# ProPrj_Electric_Dog.net
KiCad netlist of a schematic drawn in EasyEDA Pro
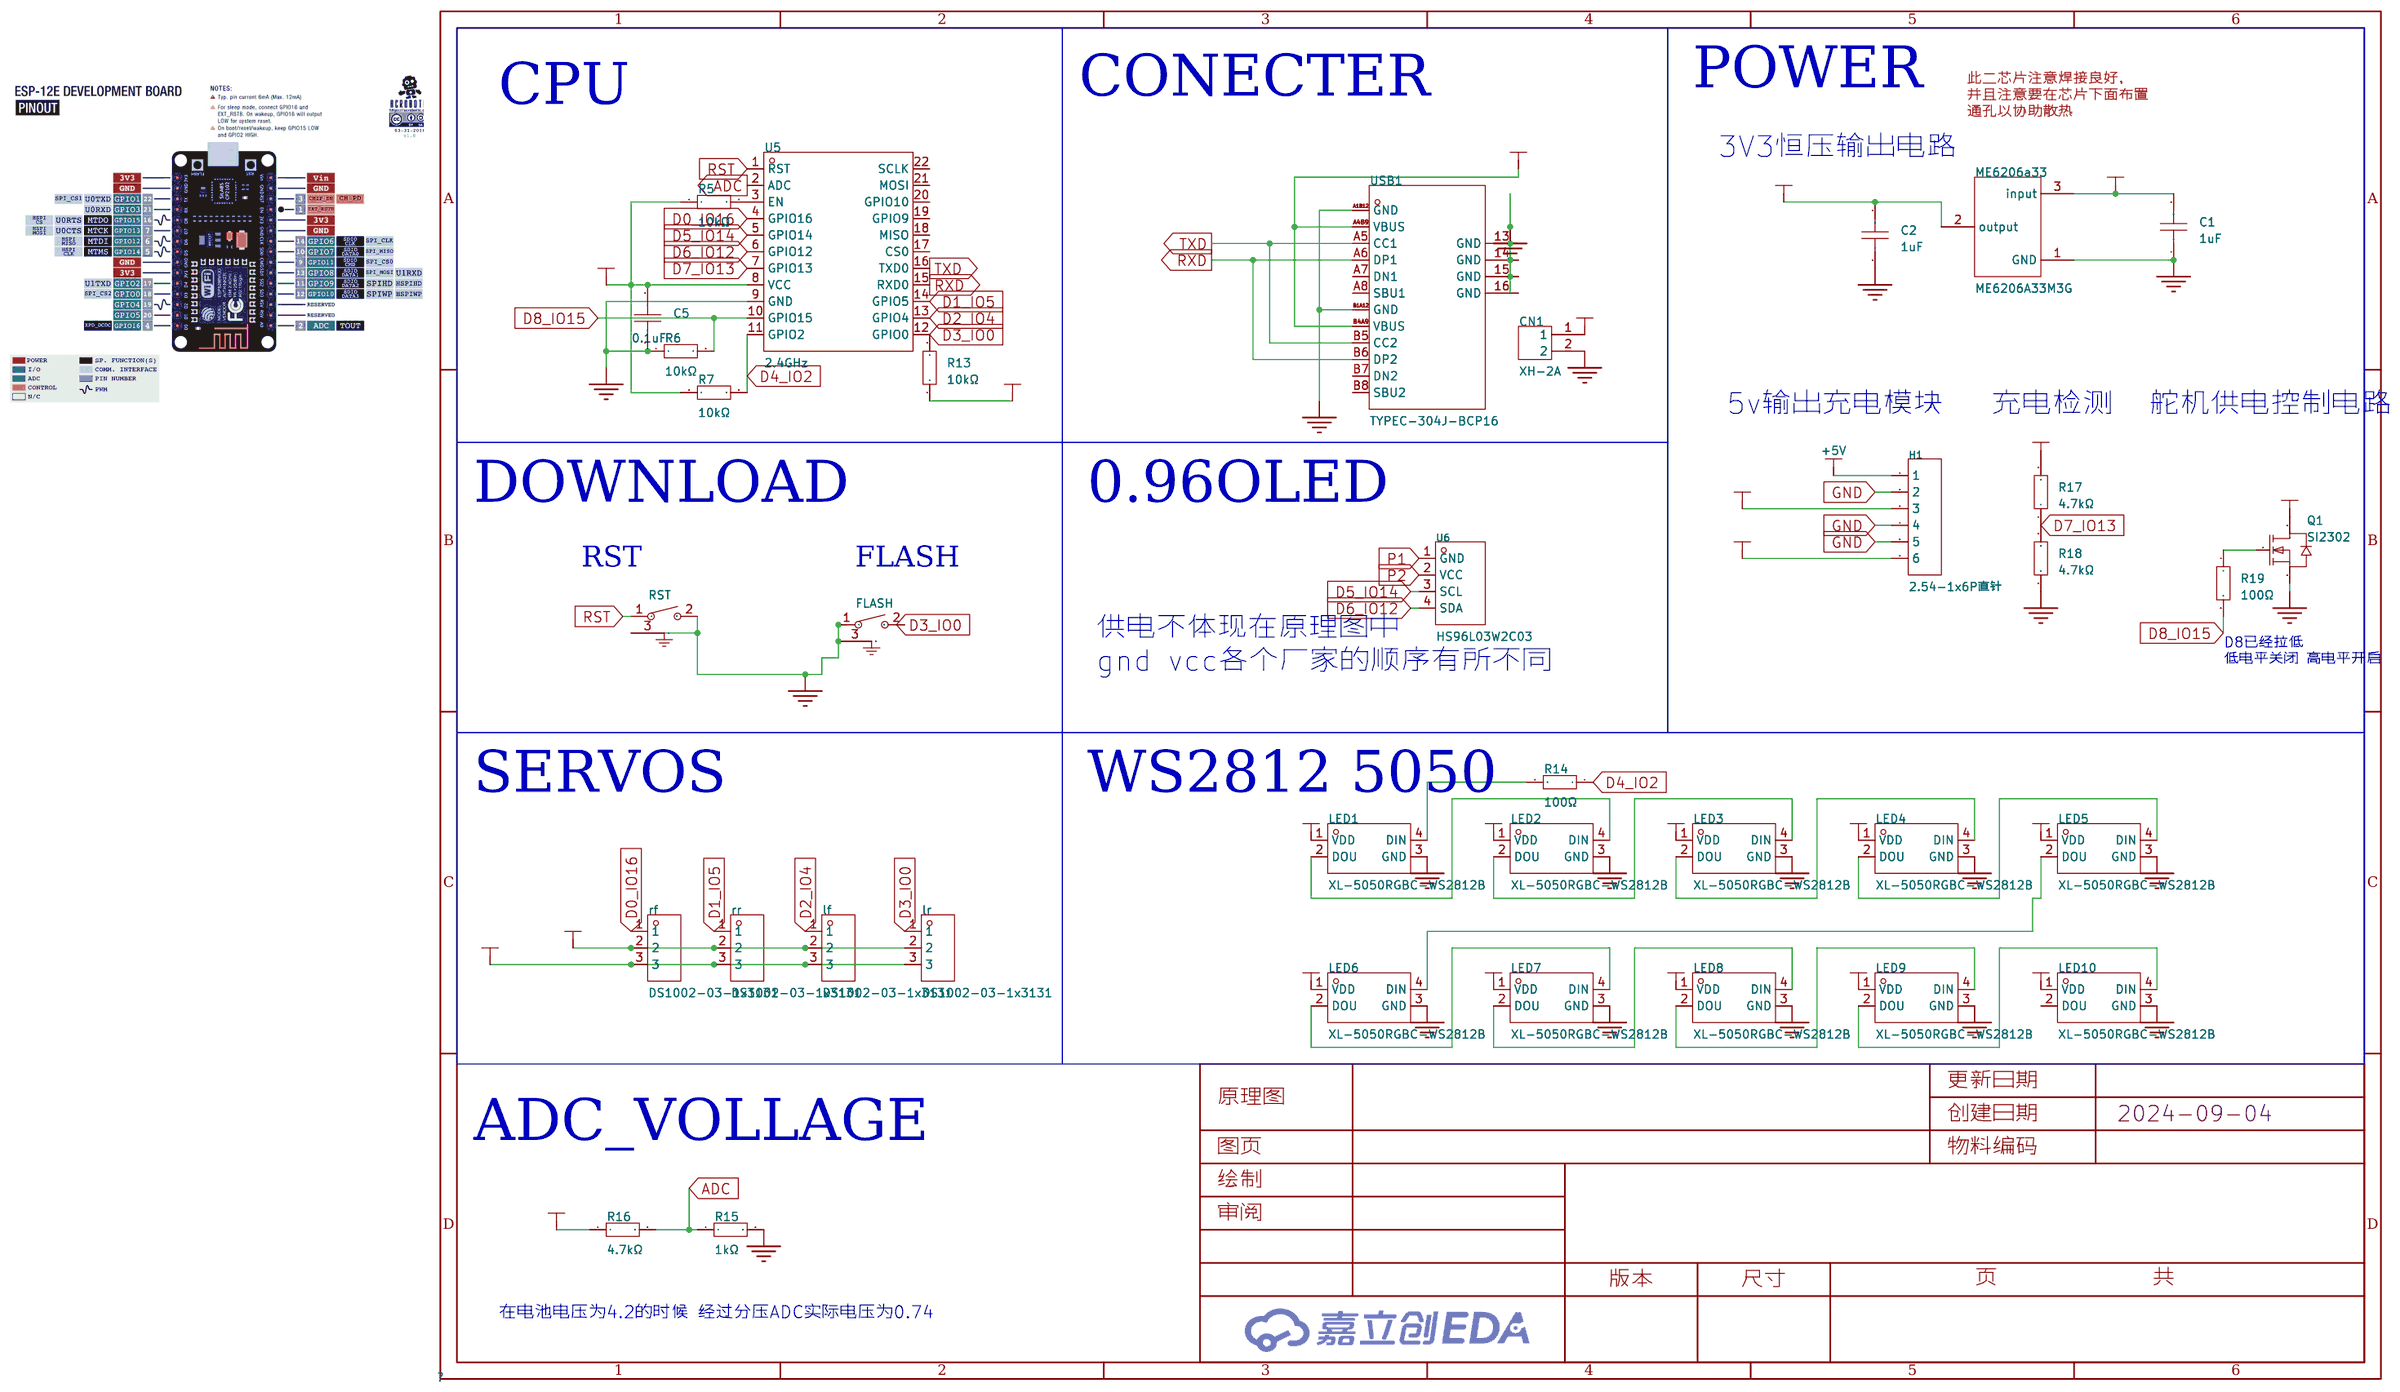
[diagram p0: schematic sheet]

(export (version "E")
  (design (tool "Eeschema 10.0.6"))
  (components
    (comp (ref "C1")
      (value "1uF")
      (footprint "easyedapro:C0603")
      (description "容值:1uF;精度:±10%;额定电压:50V;材质(温度系数):X5R;")
      (fields
        (field (name "Manufacturer Part") "CL10A105KB8NNNC")
        (field (name "Manufacturer") "SAMSUNG(三星)")
      )
      (libsource (lib "easyedapro") (part "CL10A105KB8NNNC"))
    )
    (comp (ref "C2")
      (value "1uF")
      (footprint "easyedapro:C0603")
      (description "容值:1uF;精度:±10%;额定电压:50V;材质(温度系数):X5R;")
      (fields
        (field (name "Manufacturer Part") "CL10A105KB8NNNC")
        (field (name "Manufacturer") "SAMSUNG(三星)")
      )
      (libsource (lib "easyedapro") (part "CL10A105KB8NNNC"))
    )
    (comp (ref "C5")
      (value "0.1uF")
      (footprint "easyedapro:C0603")
      (description "容值:0.1uF;精度:±10%;额定电压:50V;温度系数:-;")
      (fields
        (field (name "Manufacturer Part") "0603BB104K500NGT")
        (field (name "Manufacturer") "Knowles(楼氏)")
      )
      (libsource (lib "easyedapro") (part "0603BB104K500NGT"))
    )
    (comp (ref "CN1")
      (value "XH-2A")
      (footprint "easyedapro:CONN-TH_XH-2A")
      (description "插针结构:1x2P;间距:2.5mm;安装方式:-;参考系列:XH;总PIN数:2P;排数:1;每排PIN数:2;行距:-;触头材质:-;")
      (fields (field (name "Manufacturer") "BOOMELE(博穆精密)"))
      (libsource (lib "easyedapro") (part "XH-2A"))
    )
    (comp (ref "FLASH")
      (value "TS-1091B-A8B3-D2")
      (footprint "easyedapro:KEY-TH_L4.5-W6.5-P3.10_TS-1091B-A8B3-D2")
      (description "电路结构:单刀单掷;安装方式:卧插;作用力:250gf@±30gf;机械寿命:-;带支架:否;")
      (fields (field (name "Manufacturer") "Yuandi(元迪)"))
      (libsource (lib "easyedapro") (part "TS-1091B-A8B3-D2"))
    )
    (comp (ref "H1")
      (value "2.54-1x6P直针")
      (footprint "easyedapro:HDR-TH_6P-P2.54-V-M-1")
      (fields (field (name "Manufacturer") "BOOMELE(博穆精密)"))
      (libsource (lib "easyedapro") (part "Header-Male-2.54_1x6"))
    )
    (comp (ref "LED1")
      (value "XL-5050RGBC-WS2812B")
      (footprint "easyedapro:LED-SMD_4P-L5.0-W5.0-BL_XL-5050RGBC")
      (description "5050七彩幻彩透明贴片LED灯珠 5050 幻彩透明四脚 ws2812B 内置驱动IC")
      (fields (field (name "Manufacturer") "XINGLIGHT(成兴光)"))
      (libsource (lib "easyedapro") (part "XL-5050RGBC-WS2812B"))
    )
    (comp (ref "LED2")
      (value "XL-5050RGBC-WS2812B")
      (footprint "easyedapro:LED-SMD_4P-L5.0-W5.0-BL_XL-5050RGBC")
      (description "5050七彩幻彩透明贴片LED灯珠 5050 幻彩透明四脚 ws2812B 内置驱动IC")
      (fields (field (name "Manufacturer") "XINGLIGHT(成兴光)"))
      (libsource (lib "easyedapro") (part "XL-5050RGBC-WS2812B"))
    )
    (comp (ref "LED3")
      (value "XL-5050RGBC-WS2812B")
      (footprint "easyedapro:LED-SMD_4P-L5.0-W5.0-BL_XL-5050RGBC")
      (description "5050七彩幻彩透明贴片LED灯珠 5050 幻彩透明四脚 ws2812B 内置驱动IC")
      (fields (field (name "Manufacturer") "XINGLIGHT(成兴光)"))
      (libsource (lib "easyedapro") (part "XL-5050RGBC-WS2812B"))
    )
    (comp (ref "LED4")
      (value "XL-5050RGBC-WS2812B")
      (footprint "easyedapro:LED-SMD_4P-L5.0-W5.0-BL_XL-5050RGBC")
      (description "5050七彩幻彩透明贴片LED灯珠 5050 幻彩透明四脚 ws2812B 内置驱动IC")
      (fields (field (name "Manufacturer") "XINGLIGHT(成兴光)"))
      (libsource (lib "easyedapro") (part "XL-5050RGBC-WS2812B"))
    )
    (comp (ref "LED5")
      (value "XL-5050RGBC-WS2812B")
      (footprint "easyedapro:LED-SMD_4P-L5.0-W5.0-BL_XL-5050RGBC")
      (description "5050七彩幻彩透明贴片LED灯珠 5050 幻彩透明四脚 ws2812B 内置驱动IC")
      (fields (field (name "Manufacturer") "XINGLIGHT(成兴光)"))
      (libsource (lib "easyedapro") (part "XL-5050RGBC-WS2812B"))
    )
    (comp (ref "LED6")
      (value "XL-5050RGBC-WS2812B")
      (footprint "easyedapro:LED-SMD_4P-L5.0-W5.0-BL_XL-5050RGBC")
      (description "5050七彩幻彩透明贴片LED灯珠 5050 幻彩透明四脚 ws2812B 内置驱动IC")
      (fields (field (name "Manufacturer") "XINGLIGHT(成兴光)"))
      (libsource (lib "easyedapro") (part "XL-5050RGBC-WS2812B"))
    )
    (comp (ref "LED7")
      (value "XL-5050RGBC-WS2812B")
      (footprint "easyedapro:LED-SMD_4P-L5.0-W5.0-BL_XL-5050RGBC")
      (description "5050七彩幻彩透明贴片LED灯珠 5050 幻彩透明四脚 ws2812B 内置驱动IC")
      (fields (field (name "Manufacturer") "XINGLIGHT(成兴光)"))
      (libsource (lib "easyedapro") (part "XL-5050RGBC-WS2812B"))
    )
    (comp (ref "LED8")
      (value "XL-5050RGBC-WS2812B")
      (footprint "easyedapro:LED-SMD_4P-L5.0-W5.0-BL_XL-5050RGBC")
      (description "5050七彩幻彩透明贴片LED灯珠 5050 幻彩透明四脚 ws2812B 内置驱动IC")
      (fields (field (name "Manufacturer") "XINGLIGHT(成兴光)"))
      (libsource (lib "easyedapro") (part "XL-5050RGBC-WS2812B"))
    )
    (comp (ref "LED9")
      (value "XL-5050RGBC-WS2812B")
      (footprint "easyedapro:LED-SMD_4P-L5.0-W5.0-BL_XL-5050RGBC")
      (description "5050七彩幻彩透明贴片LED灯珠 5050 幻彩透明四脚 ws2812B 内置驱动IC")
      (fields (field (name "Manufacturer") "XINGLIGHT(成兴光)"))
      (libsource (lib "easyedapro") (part "XL-5050RGBC-WS2812B"))
    )
    (comp (ref "LED10")
      (value "XL-5050RGBC-WS2812B")
      (footprint "easyedapro:LED-SMD_4P-L5.0-W5.0-BL_XL-5050RGBC")
      (description "5050七彩幻彩透明贴片LED灯珠 5050 幻彩透明四脚 ws2812B 内置驱动IC")
      (fields (field (name "Manufacturer") "XINGLIGHT(成兴光)"))
      (libsource (lib "easyedapro") (part "XL-5050RGBC-WS2812B"))
    )
    (comp (ref "lf")
      (value "DS1002-03-1x3131")
      (footprint "easyedapro:HDR-TH_3P-P2.54-V-M-1")
      (description "端子镀锡150u\\\"六爪镀金")
      (fields (field (name "Manufacturer") "CONNFLY"))
      (libsource (lib "easyedapro") (part "DS1002-03-1X3131"))
    )
    (comp (ref "lr")
      (value "DS1002-03-1x3131")
      (footprint "easyedapro:HDR-TH_3P-P2.54-V-M-1")
      (description "端子镀锡150u\\\"六爪镀金")
      (fields (field (name "Manufacturer") "CONNFLY"))
      (libsource (lib "easyedapro") (part "DS1002-03-1X3131"))
    )
    (comp (ref "ME6206a33")
      (value "ME6206A33M3G")
      (footprint "easyedapro:SOT-23-3_L2.9-W1.6-P1.90-LS2.8-BR")
      (description "输出类型:固定;输出极性:正;最大输入电压:6V;输出电压:3.3V;输出电流:300mA;电源纹波抑制比(PSRR):50dB@(1kHz);")
      (fields (field (name "Manufacturer") "MICRONE(南京微盟)"))
      (libsource (lib "easyedapro") (part "ME6206A33M3G"))
    )
    (comp (ref "Q1")
      (value "SI2302")
      (footprint "easyedapro:SOT-23-3_L2.9-W1.3-P1.90-LS2.4-BR")
      (fields (field (name "Manufacturer") "HXY MOSFET(华轩阳电子)"))
      (libsource (lib "easyedapro") (part "SI2302_C4748714"))
    )
    (comp (ref "R5")
      (value "10kΩ")
      (footprint "easyedapro:R0603")
      (description "电阻类型:厚膜电阻;阻值:10kΩ;精度:±1%;功率:100mW;")
      (fields
        (field (name "Manufacturer Part") "0603WAF1002T5E")
        (field (name "Manufacturer") "UNI-ROYAL(厚声)")
      )
      (libsource (lib "easyedapro") (part "0603WAF1002T5E"))
    )
    (comp (ref "R6")
      (value "10kΩ")
      (footprint "easyedapro:R0603")
      (description "电阻类型:厚膜电阻;阻值:10kΩ;精度:±1%;功率:100mW;")
      (fields
        (field (name "Manufacturer Part") "0603WAF1002T5E")
        (field (name "Manufacturer") "UNI-ROYAL(厚声)")
      )
      (libsource (lib "easyedapro") (part "0603WAF1002T5E"))
    )
    (comp (ref "R7")
      (value "10kΩ")
      (footprint "easyedapro:R0603")
      (description "电阻类型:厚膜电阻;阻值:10kΩ;精度:±1%;功率:100mW;")
      (fields
        (field (name "Manufacturer Part") "0603WAF1002T5E")
        (field (name "Manufacturer") "UNI-ROYAL(厚声)")
      )
      (libsource (lib "easyedapro") (part "0603WAF1002T5E"))
    )
    (comp (ref "R13")
      (value "10kΩ")
      (footprint "easyedapro:R0603")
      (description "电阻类型:厚膜电阻;阻值:10kΩ;精度:±1%;功率:100mW;")
      (fields
        (field (name "Manufacturer Part") "0603WAF1002T5E")
        (field (name "Manufacturer") "UNI-ROYAL(厚声)")
      )
      (libsource (lib "easyedapro") (part "0603WAF1002T5E"))
    )
    (comp (ref "R14")
      (value "100Ω")
      (footprint "easyedapro:R0603")
      (description "电阻类型:厚膜电阻;阻值:100Ω;精度:±1%;功率:100mW;最大工作电压:75V;温度系数:±200ppm/°C;")
      (fields
        (field (name "Manufacturer Part") "0603WAF1000T5E")
        (field (name "Manufacturer") "UNI-ROYAL(厚声)")
      )
      (libsource (lib "easyedapro") (part "0603WAF1000T5E"))
    )
    (comp (ref "R15")
      (value "1kΩ")
      (footprint "easyedapro:R0603")
      (description "电阻类型:厚膜电阻;阻值:1kΩ;精度:±1%;功率:100mW;")
      (fields
        (field (name "Manufacturer Part") "0603WAF1001T5E")
        (field (name "Manufacturer") "UNI-ROYAL(厚声)")
      )
      (libsource (lib "easyedapro") (part "0603WAF1001T5E"))
    )
    (comp (ref "R16")
      (value "4.7kΩ")
      (footprint "easyedapro:R0603")
      (description "电阻类型:厚膜电阻;阻值:4.7kΩ;精度:±1%;功率:100mW;最大工作电压:75V;温度系数:±100ppm/°C;")
      (fields
        (field (name "Manufacturer Part") "0603WAF4701T5E")
        (field (name "Manufacturer") "UNI-ROYAL(厚声)")
      )
      (libsource (lib "easyedapro") (part "0603WAF4701T5E"))
    )
    (comp (ref "R17")
      (value "4.7kΩ")
      (footprint "easyedapro:R0603")
      (description "电阻类型:厚膜电阻;阻值:4.7kΩ;精度:±1%;功率:100mW;最大工作电压:75V;温度系数:±100ppm/°C;")
      (fields
        (field (name "Manufacturer Part") "0603WAF4701T5E")
        (field (name "Manufacturer") "UNI-ROYAL(厚声)")
      )
      (libsource (lib "easyedapro") (part "0603WAF4701T5E"))
    )
    (comp (ref "R18")
      (value "4.7kΩ")
      (footprint "easyedapro:R0603")
      (description "电阻类型:厚膜电阻;阻值:4.7kΩ;精度:±1%;功率:100mW;最大工作电压:75V;温度系数:±100ppm/°C;")
      (fields
        (field (name "Manufacturer Part") "0603WAF4701T5E")
        (field (name "Manufacturer") "UNI-ROYAL(厚声)")
      )
      (libsource (lib "easyedapro") (part "0603WAF4701T5E"))
    )
    (comp (ref "R19")
      (value "100Ω")
      (footprint "easyedapro:R0603")
      (description "电阻类型:厚膜电阻;阻值:100Ω;精度:±1%;功率:100mW;最大工作电压:75V;温度系数:±200ppm/°C;")
      (fields
        (field (name "Manufacturer Part") "0603WAF1000T5E")
        (field (name "Manufacturer") "UNI-ROYAL(厚声)")
      )
      (libsource (lib "easyedapro") (part "0603WAF1000T5E"))
    )
    (comp (ref "rf")
      (value "DS1002-03-1x3131")
      (footprint "easyedapro:HDR-TH_3P-P2.54-V-M-1")
      (description "端子镀锡150u\\\"六爪镀金")
      (fields (field (name "Manufacturer") "CONNFLY"))
      (libsource (lib "easyedapro") (part "DS1002-03-1X3131"))
    )
    (comp (ref "rr")
      (value "DS1002-03-1x3131")
      (footprint "easyedapro:HDR-TH_3P-P2.54-V-M-1")
      (description "端子镀锡150u\\\"六爪镀金")
      (fields (field (name "Manufacturer") "CONNFLY"))
      (libsource (lib "easyedapro") (part "DS1002-03-1X3131"))
    )
    (comp (ref "RST")
      (value "TS-1091B-A8B3-D2")
      (footprint "easyedapro:KEY-TH_L4.5-W6.5-P3.10_TS-1091B-A8B3-D2")
      (description "电路结构:单刀单掷;安装方式:卧插;作用力:250gf@±30gf;机械寿命:-;带支架:否;")
      (fields (field (name "Manufacturer") "Yuandi(元迪)"))
      (libsource (lib "easyedapro") (part "TS-1091B-A8B3-D2"))
    )
    (comp (ref "U5")
      (value "2.4GHz")
      (footprint "easyedapro:WIFIM-SMD_ESP-12F-ESP8266MOD")
      (description "频率:2.4GHz;发射功率:16dBm;核心处理器:ESP8266;天线形式:PCB 板载天线;接收灵敏度:-90dBm;")
      (fields
        (field (name "Manufacturer Part") "ESP-12F(ESP8266MOD)")
        (field (name "Manufacturer") "Ai-Thinker(安信可)")
      )
      (libsource (lib "easyedapro") (part "ESP-12F(ESP8266MOD)"))
    )
    (comp (ref "U6")
      (value "HS96L03W2C03")
      (footprint "easyedapro:OLED-TH_L27.8-W27.2-P2.54_C9900033791")
      (fields (field (name "Manufacturer") "HS(汉昇)"))
      (libsource (lib "easyedapro") (part "HS96L03W2C03"))
    )
    (comp (ref "USB1")
      (value "TYPEC-304J-BCP16")
      (footprint "easyedapro:USB-C-SMD_TYPEC-304J-BCP16")
      (fields (field (name "Manufacturer") "XUNPU(讯普)"))
      (libsource (lib "easyedapro") (part "TYPEC-304J-BCP16"))
    )
  )
  (nets
    (net (code "1") (name "+5V") (class "Default")
      (node (ref "H1") (pin "1") (pinfunction "1_1") (pintype "input"))
    )
    (net (code "2") (name "3V3") (class "Default")
      (node (ref "C2") (pin "2") (pinfunction "2_2") (pintype "unspecified"))
      (node (ref "C5") (pin "2") (pinfunction "2_2") (pintype "input"))
      (node (ref "LED1") (pin "1") (pinfunction "VDD_1") (pintype "unspecified"))
      (node (ref "LED10") (pin "1") (pinfunction "VDD_1") (pintype "unspecified"))
      (node (ref "LED2") (pin "1") (pinfunction "VDD_1") (pintype "unspecified"))
      (node (ref "LED3") (pin "1") (pinfunction "VDD_1") (pintype "unspecified"))
      (node (ref "LED4") (pin "1") (pinfunction "VDD_1") (pintype "unspecified"))
      (node (ref "LED5") (pin "1") (pinfunction "VDD_1") (pintype "unspecified"))
      (node (ref "LED6") (pin "1") (pinfunction "VDD_1") (pintype "unspecified"))
      (node (ref "LED7") (pin "1") (pinfunction "VDD_1") (pintype "unspecified"))
      (node (ref "LED8") (pin "1") (pinfunction "VDD_1") (pintype "unspecified"))
      (node (ref "LED9") (pin "1") (pinfunction "VDD_1") (pintype "unspecified"))
      (node (ref "ME6206a33") (pin "2") (pinfunction "output_2") (pintype "input"))
      (node (ref "R13") (pin "1") (pinfunction "1_1") (pintype "input"))
      (node (ref "R5") (pin "1") (pinfunction "1_1") (pintype "input"))
      (node (ref "R7") (pin "1") (pinfunction "1_1") (pintype "input"))
      (node (ref "U5") (pin "8") (pinfunction "VCC_8") (pintype "input"))
    )
    (net (code "3") (name "ADC") (class "Default")
      (node (ref "R15") (pin "1") (pinfunction "1_1") (pintype "input"))
      (node (ref "R16") (pin "2") (pinfunction "2_2") (pintype "input"))
      (node (ref "U5") (pin "2") (pinfunction "ADC_2") (pintype "input"))
    )
    (net (code "4") (name "BATTERY+") (class "Default")
      (node (ref "C1") (pin "2") (pinfunction "2_2") (pintype "unspecified"))
      (node (ref "CN1") (pin "1") (pinfunction "1_1") (pintype "unspecified"))
      (node (ref "H1") (pin "3") (pinfunction "3_3") (pintype "input"))
      (node (ref "ME6206a33") (pin "3") (pinfunction "input_3") (pintype "input"))
      (node (ref "R16") (pin "1") (pinfunction "1_1") (pintype "input"))
      (node (ref "lf") (pin "2") (pinfunction "2_2") (pintype "unspecified"))
      (node (ref "lr") (pin "2") (pinfunction "2_2") (pintype "unspecified"))
      (node (ref "rf") (pin "2") (pinfunction "2_2") (pintype "unspecified"))
      (node (ref "rr") (pin "2") (pinfunction "2_2") (pintype "unspecified"))
    )
    (net (code "5") (name "D0_IO16") (class "Default")
      (node (ref "U5") (pin "4") (pinfunction "GPIO16_4") (pintype "input"))
      (node (ref "rf") (pin "1") (pinfunction "1_1") (pintype "unspecified"))
    )
    (net (code "6") (name "D1_IO5") (class "Default")
      (node (ref "U5") (pin "14") (pinfunction "GPIO5_14") (pintype "input"))
      (node (ref "rr") (pin "1") (pinfunction "1_1") (pintype "unspecified"))
    )
    (net (code "7") (name "D2_IO4") (class "Default")
      (node (ref "U5") (pin "13") (pinfunction "GPIO4_13") (pintype "input"))
      (node (ref "lf") (pin "1") (pinfunction "1_1") (pintype "unspecified"))
    )
    (net (code "8") (name "D3_IO0") (class "Default")
      (node (ref "FLASH") (pin "2") (pinfunction "2_2") (pintype "input"))
      (node (ref "R13") (pin "2") (pinfunction "2_2") (pintype "input"))
      (node (ref "U5") (pin "12") (pinfunction "GPIO0_12") (pintype "input"))
      (node (ref "lr") (pin "1") (pinfunction "1_1") (pintype "unspecified"))
    )
    (net (code "9") (name "D4_IO2") (class "Default")
      (node (ref "R14") (pin "1") (pinfunction "1_1") (pintype "input"))
      (node (ref "R7") (pin "2") (pinfunction "2_2") (pintype "input"))
      (node (ref "U5") (pin "11") (pinfunction "GPIO2_11") (pintype "input"))
    )
    (net (code "10") (name "D5_IO14") (class "Default")
      (node (ref "U5") (pin "5") (pinfunction "GPIO14_5") (pintype "input"))
      (node (ref "U6") (pin "3") (pinfunction "SCL_3") (pintype "input"))
    )
    (net (code "11") (name "D6_IO12") (class "Default")
      (node (ref "U5") (pin "6") (pinfunction "GPIO12_6") (pintype "input"))
      (node (ref "U6") (pin "4") (pinfunction "SDA_4") (pintype "input"))
    )
    (net (code "12") (name "D7_IO13") (class "Default")
      (node (ref "R17") (pin "1") (pinfunction "1_1") (pintype "input"))
      (node (ref "R18") (pin "2") (pinfunction "2_2") (pintype "input"))
      (node (ref "U5") (pin "7") (pinfunction "GPIO13_7") (pintype "input"))
    )
    (net (code "13") (name "D8_IO15") (class "Default")
      (node (ref "R19") (pin "2") (pinfunction "2_2") (pintype "input"))
      (node (ref "R6") (pin "2") (pinfunction "2_2") (pintype "input"))
      (node (ref "U5") (pin "10") (pinfunction "GPIO15_10") (pintype "input"))
    )
    (net (code "14") (name "GND") (class "Default")
      (node (ref "C1") (pin "1") (pinfunction "1_1") (pintype "unspecified"))
      (node (ref "C2") (pin "1") (pinfunction "1_1") (pintype "unspecified"))
      (node (ref "C5") (pin "1") (pinfunction "1_1") (pintype "input"))
      (node (ref "CN1") (pin "2") (pinfunction "2_2") (pintype "unspecified"))
      (node (ref "FLASH") (pin "1") (pinfunction "1_1") (pintype "input"))
      (node (ref "FLASH") (pin "3") (pinfunction "GND_3") (pintype "input"))
      (node (ref "H1") (pin "2") (pinfunction "2_2") (pintype "input"))
      (node (ref "H1") (pin "4") (pinfunction "4_4") (pintype "input"))
      (node (ref "H1") (pin "5") (pinfunction "5_5") (pintype "input"))
      (node (ref "LED1") (pin "3") (pinfunction "GND_3") (pintype "unspecified"))
      (node (ref "LED10") (pin "3") (pinfunction "GND_3") (pintype "unspecified"))
      (node (ref "LED2") (pin "3") (pinfunction "GND_3") (pintype "unspecified"))
      (node (ref "LED3") (pin "3") (pinfunction "GND_3") (pintype "unspecified"))
      (node (ref "LED4") (pin "3") (pinfunction "GND_3") (pintype "unspecified"))
      (node (ref "LED5") (pin "3") (pinfunction "GND_3") (pintype "unspecified"))
      (node (ref "LED6") (pin "3") (pinfunction "GND_3") (pintype "unspecified"))
      (node (ref "LED7") (pin "3") (pinfunction "GND_3") (pintype "unspecified"))
      (node (ref "LED8") (pin "3") (pinfunction "GND_3") (pintype "unspecified"))
      (node (ref "LED9") (pin "3") (pinfunction "GND_3") (pintype "unspecified"))
      (node (ref "ME6206a33") (pin "1") (pinfunction "GND_1") (pintype "input"))
      (node (ref "Q1") (pin "2") (pinfunction "S_2") (pintype "unspecified"))
      (node (ref "R15") (pin "2") (pinfunction "2_2") (pintype "input"))
      (node (ref "R18") (pin "1") (pinfunction "1_1") (pintype "input"))
      (node (ref "R6") (pin "1") (pinfunction "1_1") (pintype "input"))
      (node (ref "RST") (pin "2") (pinfunction "2_2") (pintype "input"))
      (node (ref "RST") (pin "3") (pinfunction "GND_3") (pintype "input"))
      (node (ref "U5") (pin "9") (pinfunction "GND_9") (pintype "input"))
      (node (ref "USB1") (pin "13") (pinfunction "GND_13") (pintype "input"))
      (node (ref "USB1") (pin "14") (pinfunction "GND_14") (pintype "input"))
      (node (ref "USB1") (pin "15") (pinfunction "GND_15") (pintype "input"))
      (node (ref "USB1") (pin "16") (pinfunction "GND_16") (pintype "input"))
      (node (ref "USB1") (pin "A1B12") (pinfunction "GND_A1B12") (pintype "input"))
      (node (ref "USB1") (pin "B1A12") (pinfunction "GND_B1A12") (pintype "input"))
    )
    (net (code "15") (name "Net-(LED1-DIN)") (class "Default")
      (node (ref "LED1") (pin "4") (pinfunction "DIN_4") (pintype "unspecified"))
      (node (ref "R14") (pin "2") (pinfunction "2_2") (pintype "input"))
    )
    (net (code "16") (name "Net-(LED1-DOU)") (class "Default")
      (node (ref "LED1") (pin "2") (pinfunction "DOU_2") (pintype "unspecified"))
      (node (ref "LED2") (pin "4") (pinfunction "DIN_4") (pintype "unspecified"))
    )
    (net (code "17") (name "Net-(LED2-DOU)") (class "Default")
      (node (ref "LED2") (pin "2") (pinfunction "DOU_2") (pintype "unspecified"))
      (node (ref "LED3") (pin "4") (pinfunction "DIN_4") (pintype "unspecified"))
    )
    (net (code "18") (name "Net-(LED3-DOU)") (class "Default")
      (node (ref "LED3") (pin "2") (pinfunction "DOU_2") (pintype "unspecified"))
      (node (ref "LED4") (pin "4") (pinfunction "DIN_4") (pintype "unspecified"))
    )
    (net (code "19") (name "Net-(LED4-DOU)") (class "Default")
      (node (ref "LED4") (pin "2") (pinfunction "DOU_2") (pintype "unspecified"))
      (node (ref "LED5") (pin "4") (pinfunction "DIN_4") (pintype "unspecified"))
    )
    (net (code "20") (name "Net-(LED5-DOU)") (class "Default")
      (node (ref "LED5") (pin "2") (pinfunction "DOU_2") (pintype "unspecified"))
      (node (ref "LED6") (pin "4") (pinfunction "DIN_4") (pintype "unspecified"))
    )
    (net (code "21") (name "Net-(LED6-DOU)") (class "Default")
      (node (ref "LED6") (pin "2") (pinfunction "DOU_2") (pintype "unspecified"))
      (node (ref "LED7") (pin "4") (pinfunction "DIN_4") (pintype "unspecified"))
    )
    (net (code "22") (name "Net-(LED7-DOU)") (class "Default")
      (node (ref "LED7") (pin "2") (pinfunction "DOU_2") (pintype "unspecified"))
      (node (ref "LED8") (pin "4") (pinfunction "DIN_4") (pintype "unspecified"))
    )
    (net (code "23") (name "Net-(LED8-DOU)") (class "Default")
      (node (ref "LED8") (pin "2") (pinfunction "DOU_2") (pintype "unspecified"))
      (node (ref "LED9") (pin "4") (pinfunction "DIN_4") (pintype "unspecified"))
    )
    (net (code "24") (name "Net-(LED10-DIN)") (class "Default")
      (node (ref "LED10") (pin "4") (pinfunction "DIN_4") (pintype "unspecified"))
      (node (ref "LED9") (pin "2") (pinfunction "DOU_2") (pintype "unspecified"))
    )
    (net (code "25") (name "Net-(Q1-G)") (class "Default")
      (node (ref "Q1") (pin "1") (pinfunction "G_1") (pintype "unspecified"))
      (node (ref "R19") (pin "1") (pinfunction "1_1") (pintype "input"))
    )
    (net (code "26") (name "Net-(U5-EN)") (class "Default")
      (node (ref "R5") (pin "2") (pinfunction "2_2") (pintype "input"))
      (node (ref "U5") (pin "3") (pinfunction "EN_3") (pintype "input"))
    )
    (net (code "27") (name "P1") (class "Default")
      (node (ref "U6") (pin "1") (pinfunction "GND_1") (pintype "input"))
    )
    (net (code "28") (name "P2") (class "Default")
      (node (ref "U6") (pin "2") (pinfunction "VCC_2") (pintype "input"))
    )
    (net (code "29") (name "RST") (class "Default")
      (node (ref "RST") (pin "1") (pinfunction "1_1") (pintype "input"))
      (node (ref "U5") (pin "1") (pinfunction "RST_1") (pintype "input"))
    )
    (net (code "30") (name "RXD") (class "Default")
      (node (ref "U5") (pin "15") (pinfunction "RXD0_15") (pintype "input"))
      (node (ref "USB1") (pin "A6") (pinfunction "DP1_A6") (pintype "input"))
      (node (ref "USB1") (pin "B6") (pinfunction "DP2_B6") (pintype "input"))
    )
    (net (code "31") (name "SERVOS_POWER") (class "Default")
      (node (ref "Q1") (pin "3") (pinfunction "D_3") (pintype "unspecified"))
      (node (ref "lf") (pin "3") (pinfunction "3_3") (pintype "unspecified"))
      (node (ref "lr") (pin "3") (pinfunction "3_3") (pintype "unspecified"))
      (node (ref "rf") (pin "3") (pinfunction "3_3") (pintype "unspecified"))
      (node (ref "rr") (pin "3") (pinfunction "3_3") (pintype "unspecified"))
    )
    (net (code "32") (name "TXD") (class "Default")
      (node (ref "U5") (pin "16") (pinfunction "TXD0_16") (pintype "input"))
      (node (ref "USB1") (pin "A5") (pinfunction "CC1_A5") (pintype "input"))
      (node (ref "USB1") (pin "B5") (pinfunction "CC2_B5") (pintype "input"))
    )
    (net (code "33") (name "VIN") (class "Default")
      (node (ref "H1") (pin "6") (pinfunction "6_6") (pintype "input"))
      (node (ref "R17") (pin "2") (pinfunction "2_2") (pintype "input"))
      (node (ref "USB1") (pin "A4B9") (pinfunction "VBUS_A4B9") (pintype "input"))
      (node (ref "USB1") (pin "B4A9") (pinfunction "VBUS_B4A9") (pintype "input"))
    )
    (net (code "34") (name "unconnected-(LED10-DOU-Pad2)") (class "Default")
      (node (ref "LED10") (pin "2") (pinfunction "DOU_2") (pintype "unspecified"))
    )
    (net (code "35") (name "unconnected-(U5-CS0-Pad17)") (class "Default")
      (node (ref "U5") (pin "17") (pinfunction "CS0_17") (pintype "input"))
    )
    (net (code "36") (name "unconnected-(U5-GPIO9-Pad19)") (class "Default")
      (node (ref "U5") (pin "19") (pinfunction "GPIO9_19") (pintype "input"))
    )
    (net (code "37") (name "unconnected-(U5-GPIO10-Pad20)") (class "Default")
      (node (ref "U5") (pin "20") (pinfunction "GPIO10_20") (pintype "input"))
    )
    (net (code "38") (name "unconnected-(U5-MISO-Pad18)") (class "Default")
      (node (ref "U5") (pin "18") (pinfunction "MISO_18") (pintype "input"))
    )
    (net (code "39") (name "unconnected-(U5-MOSI-Pad21)") (class "Default")
      (node (ref "U5") (pin "21") (pinfunction "MOSI_21") (pintype "input"))
    )
    (net (code "40") (name "unconnected-(U5-SCLK-Pad22)") (class "Default")
      (node (ref "U5") (pin "22") (pinfunction "SCLK_22") (pintype "input"))
    )
    (net (code "41") (name "unconnected-(USB1-DN1-PadA7)") (class "Default")
      (node (ref "USB1") (pin "A7") (pinfunction "DN1_A7") (pintype "input"))
    )
    (net (code "42") (name "unconnected-(USB1-DN2-PadB7)") (class "Default")
      (node (ref "USB1") (pin "B7") (pinfunction "DN2_B7") (pintype "input"))
    )
    (net (code "43") (name "unconnected-(USB1-SBU1-PadA8)") (class "Default")
      (node (ref "USB1") (pin "A8") (pinfunction "SBU1_A8") (pintype "input"))
    )
    (net (code "44") (name "unconnected-(USB1-SBU2-PadB8)") (class "Default")
      (node (ref "USB1") (pin "B8") (pinfunction "SBU2_B8") (pintype "input"))
    )
  )
)
